# CANBed2040.net
KiCad netlist of a schematic drawn in EAGLE
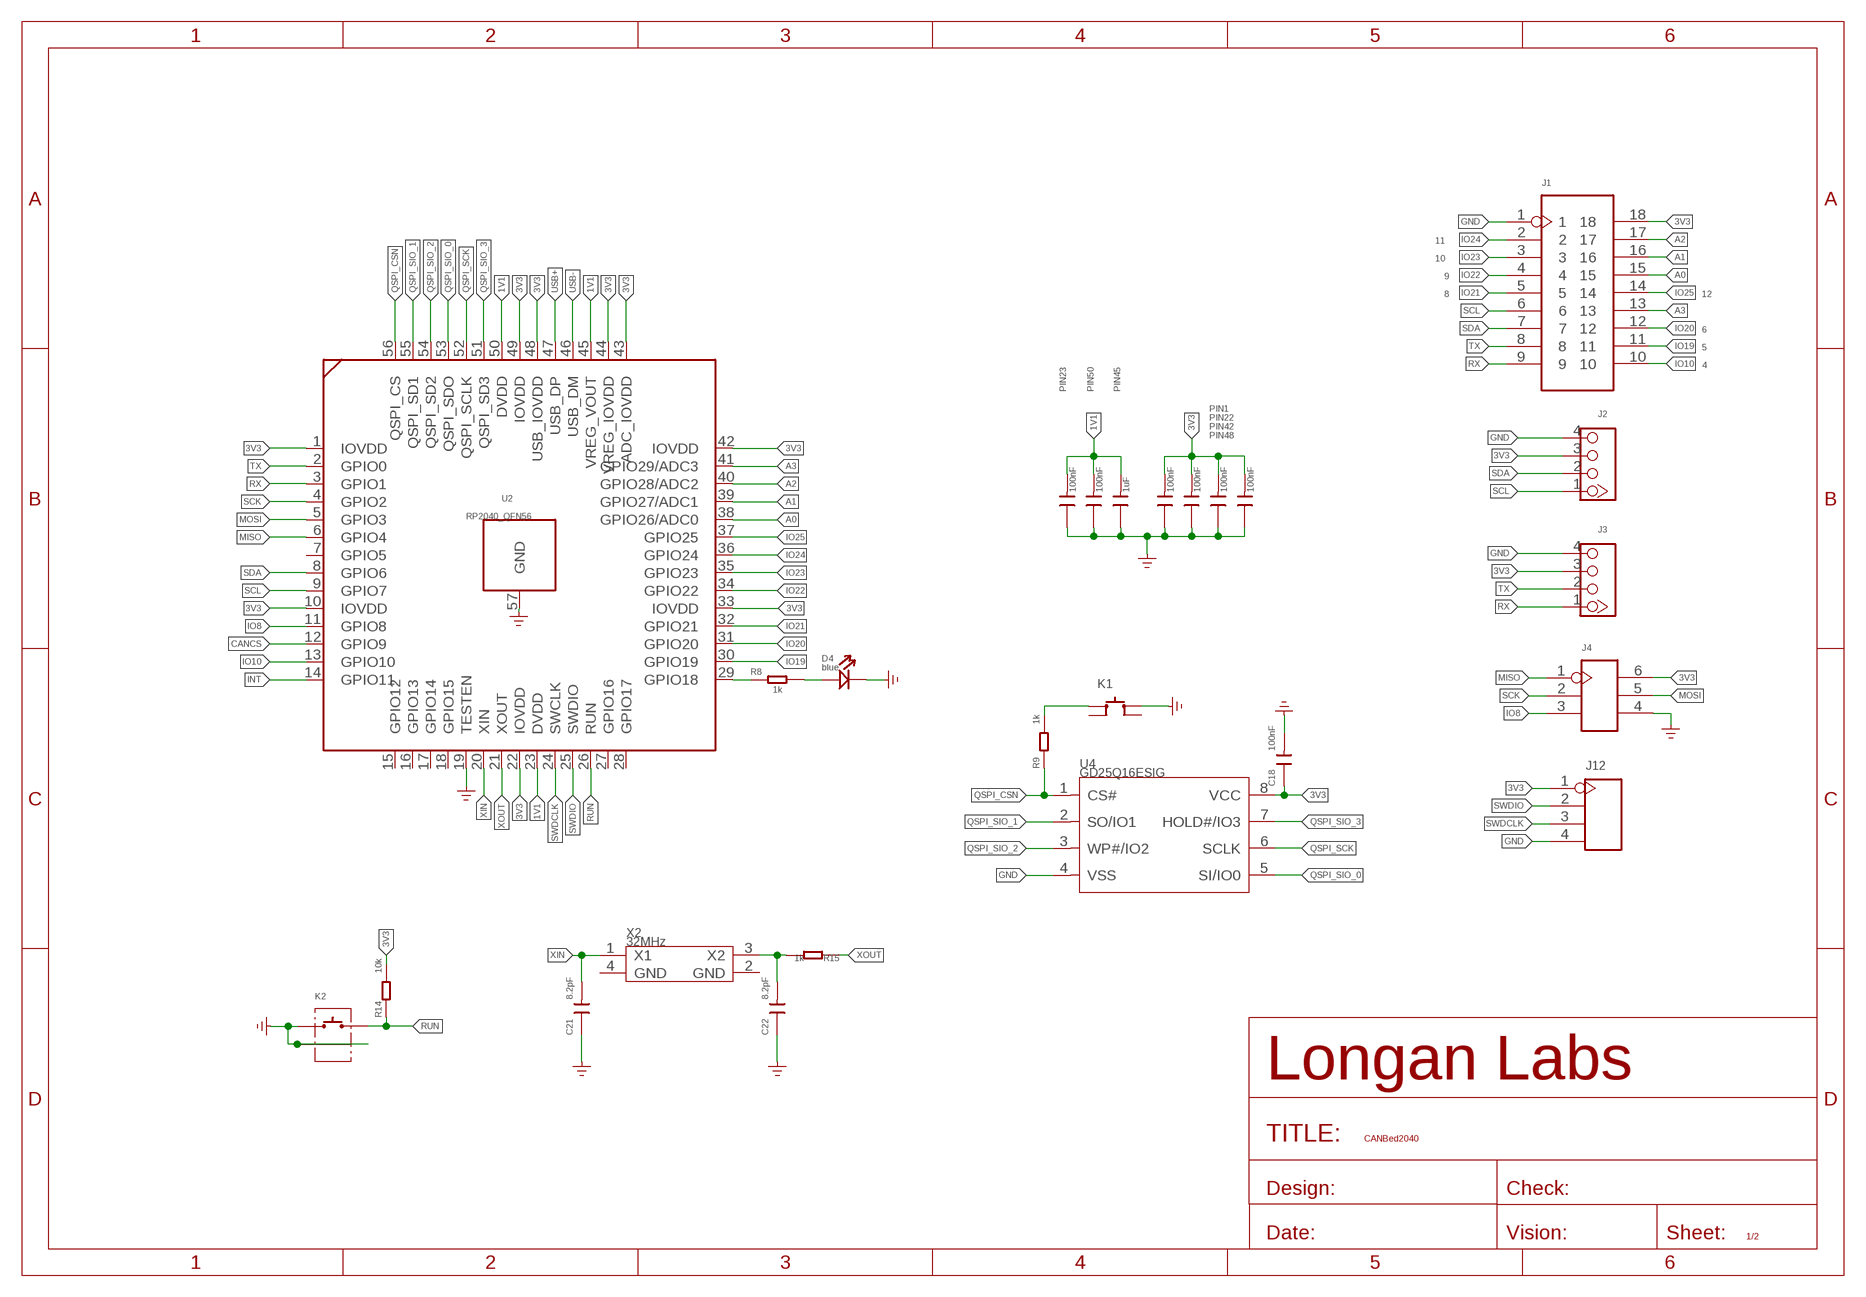
[diagram p0: schematic, sheet 1, part 1 of 2]
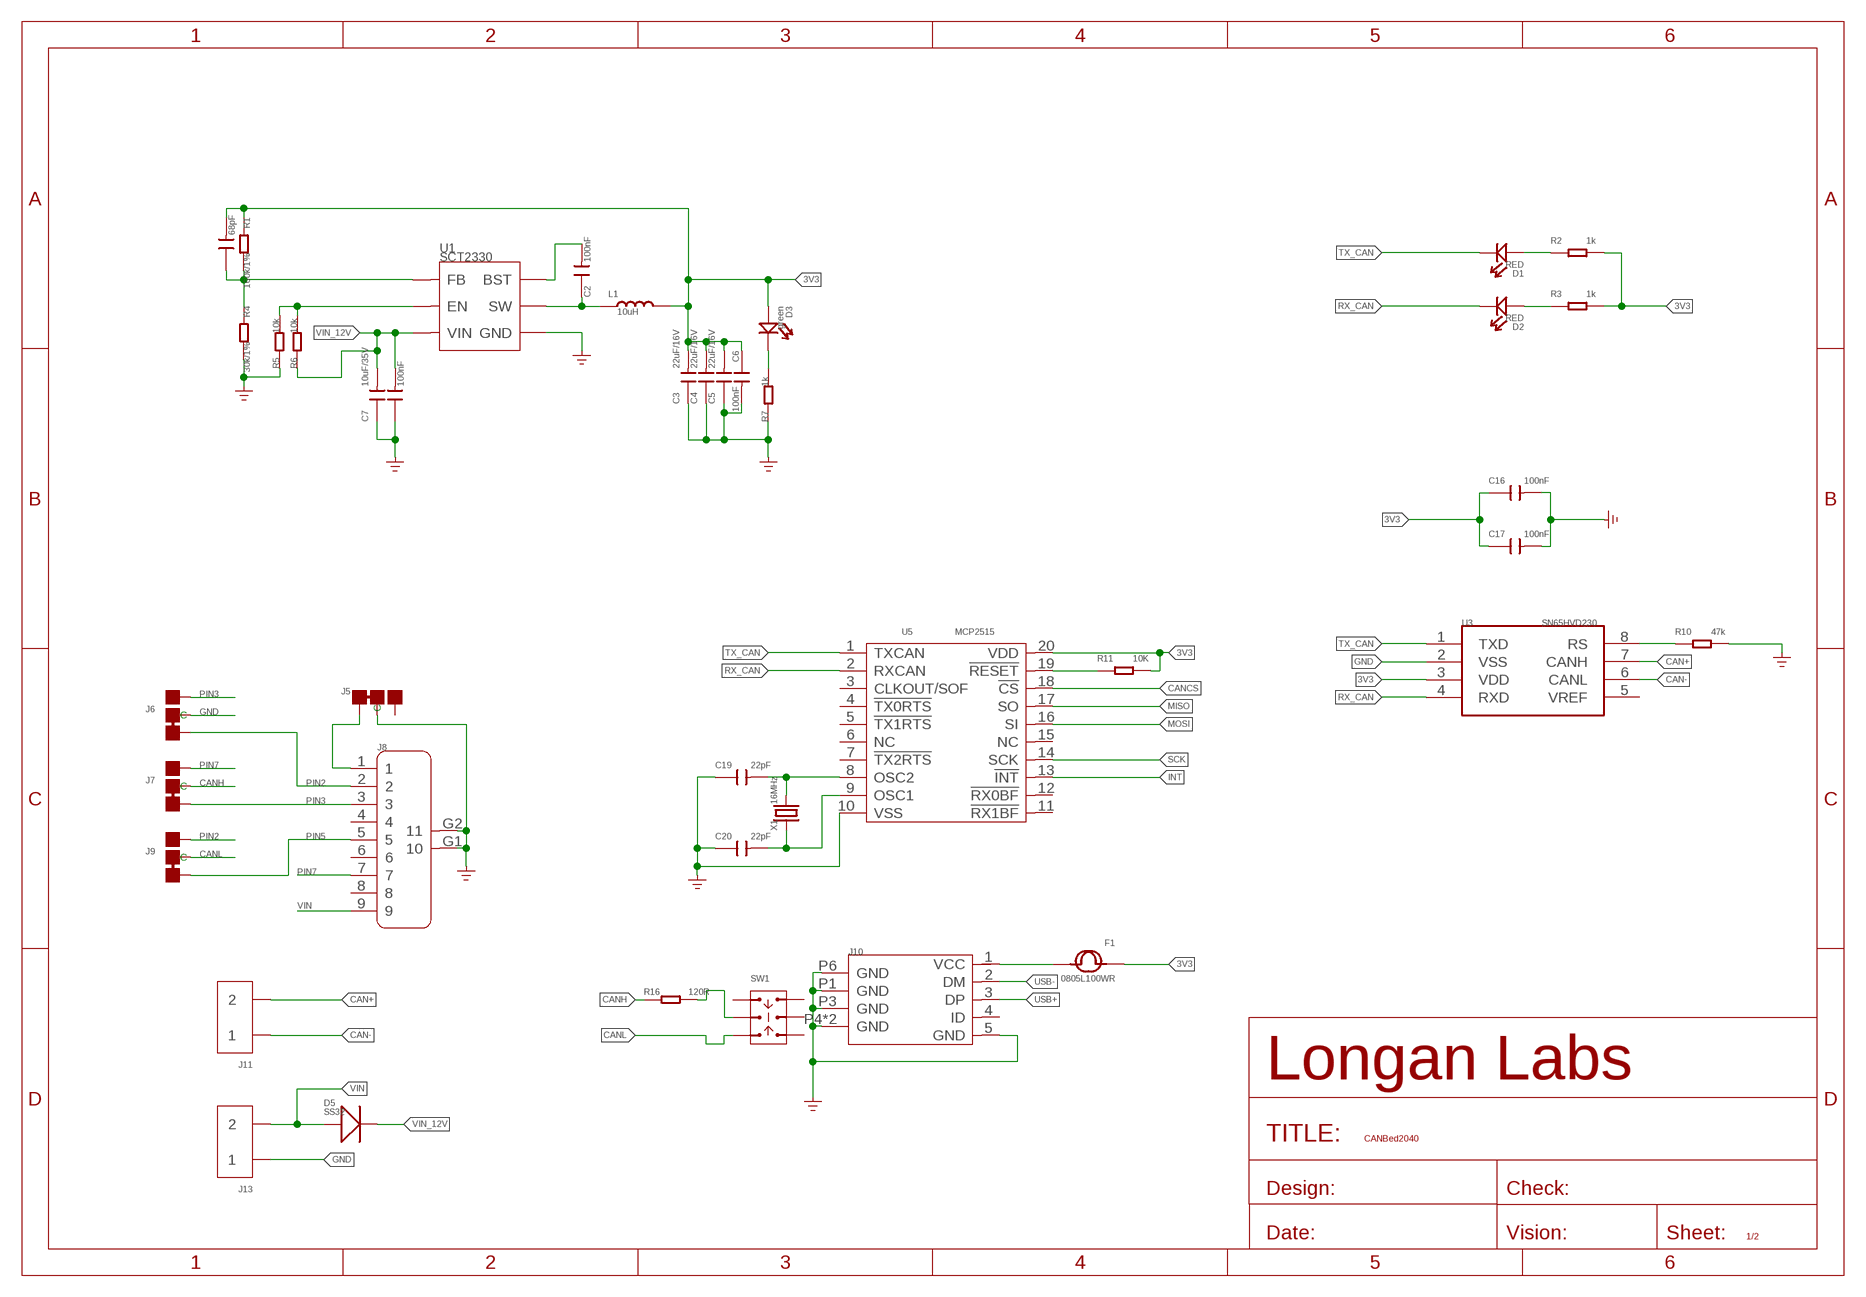
[diagram p1: schematic, sheet 1, part 2 of 2]

(export (version "E")
  (design (tool "Eeschema 10.0.6"))
  (components
    (comp (ref "C1")
      (value "68pF")
      (footprint "eagle-import:C0603")
      (libsource (lib "eagle-import") (part "CAP-0603"))
    )
    (comp (ref "C2")
      (value "100nF")
      (footprint "eagle-import:C0603")
      (libsource (lib "eagle-import") (part "CAP-0603"))
    )
    (comp (ref "C3")
      (value "22uF/16V")
      (footprint "eagle-import:C0805")
      (libsource (lib "eagle-import") (part "CAP-0805"))
    )
    (comp (ref "C4")
      (value "22uF/16V")
      (footprint "eagle-import:C0805")
      (libsource (lib "eagle-import") (part "CAP-0805"))
    )
    (comp (ref "C5")
      (value "22uF/16V")
      (footprint "eagle-import:C0805")
      (libsource (lib "eagle-import") (part "CAP-0805"))
    )
    (comp (ref "C6")
      (value "100nF")
      (footprint "eagle-import:C0603")
      (libsource (lib "eagle-import") (part "CAP-0603"))
    )
    (comp (ref "C7")
      (value "10uF/35V")
      (footprint "eagle-import:C1206")
      (libsource (lib "eagle-import") (part "CAP-1206"))
    )
    (comp (ref "C8")
      (value "100nF")
      (footprint "eagle-import:C0603")
      (libsource (lib "eagle-import") (part "CAP-0603"))
    )
    (comp (ref "C9")
      (value "100nF")
      (footprint "eagle-import:C0603")
      (libsource (lib "eagle-import") (part "CAP-0603"))
    )
    (comp (ref "C10")
      (value "100nF")
      (footprint "eagle-import:C0603")
      (libsource (lib "eagle-import") (part "CAP-0603"))
    )
    (comp (ref "C11")
      (value "1uF")
      (footprint "eagle-import:C0603")
      (libsource (lib "eagle-import") (part "CAP-0603"))
    )
    (comp (ref "C12")
      (value "100nF")
      (footprint "eagle-import:C0603")
      (libsource (lib "eagle-import") (part "CAP-0603"))
    )
    (comp (ref "C13")
      (value "100nF")
      (footprint "eagle-import:C0603")
      (libsource (lib "eagle-import") (part "CAP-0603"))
    )
    (comp (ref "C14")
      (value "100nF")
      (footprint "eagle-import:C0603")
      (libsource (lib "eagle-import") (part "CAP-0603"))
    )
    (comp (ref "C15")
      (value "100nF")
      (footprint "eagle-import:C0603")
      (libsource (lib "eagle-import") (part "CAP-0603"))
    )
    (comp (ref "C16")
      (value "100nF")
      (footprint "eagle-import:C0603")
      (libsource (lib "eagle-import") (part "CAP-0603"))
    )
    (comp (ref "C17")
      (value "100nF")
      (footprint "eagle-import:C0603")
      (libsource (lib "eagle-import") (part "CAP-0603"))
    )
    (comp (ref "C18")
      (value "100nF")
      (footprint "eagle-import:C0603")
      (libsource (lib "eagle-import") (part "CAP-0603"))
    )
    (comp (ref "C19")
      (value "22pF")
      (footprint "eagle-import:C0603")
      (libsource (lib "eagle-import") (part "CAP-0603"))
    )
    (comp (ref "C20")
      (value "22pF")
      (footprint "eagle-import:C0603")
      (libsource (lib "eagle-import") (part "CAP-0603"))
    )
    (comp (ref "C21")
      (value "8.2pF")
      (footprint "eagle-import:C0603")
      (libsource (lib "eagle-import") (part "CAP-0603"))
    )
    (comp (ref "C22")
      (value "8.2pF")
      (footprint "eagle-import:C0603")
      (libsource (lib "eagle-import") (part "CAP-0603"))
    )
    (comp (ref "D1")
      (value "RED")
      (footprint "eagle-import:LED-0603")
      (libsource (lib "eagle-import") (part "LED'0603'"))
    )
    (comp (ref "D2")
      (value "RED")
      (footprint "eagle-import:LED-0603")
      (libsource (lib "eagle-import") (part "LED'0603'"))
    )
    (comp (ref "D3")
      (value "green")
      (footprint "eagle-import:LED-0603")
      (libsource (lib "eagle-import") (part "LED'0603'"))
    )
    (comp (ref "D4")
      (value "blue")
      (footprint "eagle-import:LED-0603")
      (libsource (lib "eagle-import") (part "LED'0603'"))
    )
    (comp (ref "D5")
      (value "SS32")
      (footprint "eagle-import:DO-214AC")
      (libsource (lib "eagle-import") (part "DIODE'SMA'"))
    )
    (comp (ref "F1")
      (value "0805L100WR")
      (footprint "eagle-import:F0805")
      (libsource (lib "eagle-import") (part "FUSE0805"))
    )
    (comp (ref "J1")
      (value "HEADER-2X9P-2.54")
      (footprint "eagle-import:H2X9-2.54")
      (libsource (lib "eagle-import") (part "HEADER-2X9P-2.54"))
    )
    (comp (ref "J2")
      (value "320110033")
      (footprint "eagle-import:HW4-2.0")
      (libsource (lib "eagle-import") (part "GROVE-CONNECTOR-DIP-2.0"))
    )
    (comp (ref "J3")
      (value "320110033")
      (footprint "eagle-import:HW4-2.0")
      (libsource (lib "eagle-import") (part "GROVE-CONNECTOR-DIP-2.0"))
    )
    (comp (ref "J4")
      (value "HEADER-2X3P-2.54")
      (footprint "eagle-import:H2X3-2.54")
      (libsource (lib "eagle-import") (part "HEADER-2X3P-2.54"))
    )
    (comp (ref "J5")
      (value "JUMPER-3P-SHORT")
      (footprint "eagle-import:3P-SMD-SHORT")
      (libsource (lib "eagle-import") (part "JUMPER-3P-SHORT"))
    )
    (comp (ref "J6")
      (value "JUMPER-3P-SHORT")
      (footprint "eagle-import:3P-SMD-SHORT")
      (libsource (lib "eagle-import") (part "JUMPER-3P-SHORT"))
    )
    (comp (ref "J7")
      (value "JUMPER-3P-SHORT")
      (footprint "eagle-import:3P-SMD-SHORT")
      (libsource (lib "eagle-import") (part "JUMPER-3P-SHORT"))
    )
    (comp (ref "J8")
      (value "DB9'MEAL'")
      (footprint "eagle-import:DB9-MEAL")
      (libsource (lib "eagle-import") (part "DB9'MEAL'"))
    )
    (comp (ref "J9")
      (value "JUMPER-3P-SHORT")
      (footprint "eagle-import:3P-SMD-SHORT")
      (libsource (lib "eagle-import") (part "JUMPER-3P-SHORT"))
    )
    (comp (ref "J10")
      (value "MICRO-USB5+4P-320010050")
      (footprint "eagle-import:MICRO-USB5+5P-SMD-0.65-7.2X5.06MM")
      (libsource (lib "eagle-import") (part "MICRO-USB5+4P-320010050"))
    )
    (comp (ref "J11")
      (value "SCREW-TERMINAL-2P'5.08'")
      (footprint "eagle-import:H2-5.0-10.5X8.0MM")
      (libsource (lib "eagle-import") (part "SCREW-TERMINAL-2P'5.08'"))
    )
    (comp (ref "J12")
      (value "HEADER-4P-65/35MIL")
      (footprint "eagle-import:H4-2.54")
      (libsource (lib "eagle-import") (part "HEADER-4P-65/35MIL"))
    )
    (comp (ref "J13")
      (value "SCREW-TERMINAL-2P'5.08'")
      (footprint "eagle-import:H2-5.0-10.5X8.0MM")
      (libsource (lib "eagle-import") (part "SCREW-TERMINAL-2P'5.08'"))
    )
    (comp (ref "K1")
      (value "BUTTON-4P-4.5X4.5")
      (footprint "eagle-import:SW4-4.5X4.5X0.5MM")
      (libsource (lib "eagle-import") (part "BUTTON-4P-4.5X4.5"))
    )
    (comp (ref "K2")
      (value "BUTTON-2+2P")
      (footprint "eagle-import:SW2+2P-7.7X2.75X3.95MM")
      (libsource (lib "eagle-import") (part "BUTTON-2+2P"))
    )
    (comp (ref "L1")
      (value "10uH")
      (footprint "eagle-import:INT2-SMD-6.6X7.1X3MM")
      (libsource (lib "eagle-import") (part "INDUCTOR-6.6X7.1"))
    )
    (comp (ref "R1")
      (value "160k/1%")
      (footprint "eagle-import:R0603")
      (libsource (lib "eagle-import") (part "RES-0603"))
    )
    (comp (ref "R2")
      (value "1k")
      (footprint "eagle-import:R0603")
      (libsource (lib "eagle-import") (part "RES-0603"))
    )
    (comp (ref "R3")
      (value "1k")
      (footprint "eagle-import:R0603")
      (libsource (lib "eagle-import") (part "RES-0603"))
    )
    (comp (ref "R4")
      (value "30k/1%")
      (footprint "eagle-import:R0603")
      (libsource (lib "eagle-import") (part "RES-0603"))
    )
    (comp (ref "R5")
      (value "10k")
      (footprint "eagle-import:R0603")
      (libsource (lib "eagle-import") (part "RES-0603"))
    )
    (comp (ref "R6")
      (value "10k")
      (footprint "eagle-import:R0603")
      (libsource (lib "eagle-import") (part "RES-0603"))
    )
    (comp (ref "R7")
      (value "1k")
      (footprint "eagle-import:R0603")
      (libsource (lib "eagle-import") (part "RES-0603"))
    )
    (comp (ref "R8")
      (value "1k")
      (footprint "eagle-import:R0603")
      (libsource (lib "eagle-import") (part "RES-0603"))
    )
    (comp (ref "R9")
      (value "1k")
      (footprint "eagle-import:R0603")
      (libsource (lib "eagle-import") (part "RES-0603"))
    )
    (comp (ref "R10")
      (value "47k")
      (footprint "eagle-import:R0603")
      (libsource (lib "eagle-import") (part "RES-0603"))
    )
    (comp (ref "R11")
      (value "10K")
      (footprint "eagle-import:R0603")
      (libsource (lib "eagle-import") (part "RES-0603"))
    )
    (comp (ref "R14")
      (value "10k")
      (footprint "eagle-import:R0603")
      (libsource (lib "eagle-import") (part "RES-0603"))
    )
    (comp (ref "R15")
      (value "1k")
      (footprint "eagle-import:R0603")
      (libsource (lib "eagle-import") (part "RES-0603"))
    )
    (comp (ref "R16")
      (value "120R")
      (footprint "eagle-import:R0603")
      (libsource (lib "eagle-import") (part "RES-0603"))
    )
    (comp (ref "SW1")
      (value "SWITCH-2CH-6P-311010004")
      (footprint "eagle-import:SW6-2.54-9.0X3.5X3.2+2.0MM")
      (libsource (lib "eagle-import") (part "SWITCH-2CH-6P-311010004"))
    )
    (comp (ref "U1")
      (value "SCT2330")
      (footprint "eagle-import:SOT-23-6")
      (libsource (lib "eagle-import") (part "PMIC-SCT2330"))
    )
    (comp (ref "U2")
      (value "RP2040_QFN56")
      (footprint "eagle-import:RP2040_QFN56")
      (libsource (lib "eagle-import") (part "RP2040_QFN56"))
    )
    (comp (ref "U3")
      (value "SN65HVD230")
      (footprint "eagle-import:SOIC8-6.0")
      (libsource (lib "eagle-import") (part "MCP2551-SOIC8"))
    )
    (comp (ref "U4")
      (value "GD25Q16ESIG")
      (footprint "eagle-import:SOP8-1.27-5.3X5.25X2MM")
      (libsource (lib "eagle-import") (part "FLASH-GD25Q16E"))
    )
    (comp (ref "U5")
      (value "MCP2515")
      (footprint "eagle-import:TSSOP20-0.65-6.5X4.4MM")
      (libsource (lib "eagle-import") (part "MCP2515'ST'"))
    )
    (comp (ref "X1")
      (value "16MHz")
      (footprint "eagle-import:X4-SMD-3.2X2.5X0.7MM")
      (libsource (lib "eagle-import") (part "CRYSTAL-2P-3225"))
    )
    (comp (ref "X2")
      (value "32MHz")
      (footprint "eagle-import:X4-SMD-3.2X2.5X0.7MM")
      (libsource (lib "eagle-import") (part "CRYSTAL-4P-3225"))
    )
  )
  (nets
    (net (code "1") (name "1V1") (class "Default")
      (node (ref "C10") (pin "2") (pinfunction "2_2") (pintype "passive"))
      (node (ref "C11") (pin "2") (pinfunction "2_2") (pintype "passive"))
      (node (ref "C9") (pin "2") (pinfunction "2_2") (pintype "passive"))
      (node (ref "U2") (pin "23") (pinfunction "DVDD_23") (pintype "bidirectional"))
      (node (ref "U2") (pin "45") (pinfunction "VREG_VOUT_45") (pintype "bidirectional"))
      (node (ref "U2") (pin "50") (pinfunction "DVDD_50") (pintype "bidirectional"))
    )
    (net (code "2") (name "3V3") (class "Default")
      (node (ref "C1") (pin "2") (pinfunction "2_2") (pintype "passive"))
      (node (ref "C12") (pin "2") (pinfunction "2_2") (pintype "passive"))
      (node (ref "C13") (pin "2") (pinfunction "2_2") (pintype "passive"))
      (node (ref "C14") (pin "2") (pinfunction "2_2") (pintype "passive"))
      (node (ref "C15") (pin "2") (pinfunction "2_2") (pintype "passive"))
      (node (ref "C16") (pin "1") (pinfunction "1_1") (pintype "passive"))
      (node (ref "C17") (pin "1") (pinfunction "1_1") (pintype "passive"))
      (node (ref "C18") (pin "1") (pinfunction "1_1") (pintype "passive"))
      (node (ref "C3") (pin "2") (pinfunction "2_2") (pintype "passive"))
      (node (ref "C4") (pin "2") (pinfunction "2_2") (pintype "passive"))
      (node (ref "C5") (pin "2") (pinfunction "2_2") (pintype "passive"))
      (node (ref "C6") (pin "1") (pinfunction "1_1") (pintype "passive"))
      (node (ref "D3") (pin "+") (pinfunction "+_+") (pintype "passive"))
      (node (ref "F1") (pin "1") (pinfunction "1_1") (pintype "bidirectional"))
      (node (ref "J1") (pin "18") (pinfunction "18_18") (pintype "bidirectional"))
      (node (ref "J12") (pin "1") (pinfunction "P$1_1") (pintype "bidirectional"))
      (node (ref "J2") (pin "3") (pinfunction "3_3") (pintype "bidirectional"))
      (node (ref "J3") (pin "3") (pinfunction "3_3") (pintype "bidirectional"))
      (node (ref "J4") (pin "6") (pinfunction "6_6") (pintype "bidirectional"))
      (node (ref "L1") (pin "2") (pinfunction "2_2") (pintype "passive"))
      (node (ref "R1") (pin "1") (pinfunction "1_1") (pintype "passive"))
      (node (ref "R11") (pin "2") (pinfunction "2_2") (pintype "passive"))
      (node (ref "R14") (pin "2") (pinfunction "2_2") (pintype "passive"))
      (node (ref "R2") (pin "2") (pinfunction "2_2") (pintype "passive"))
      (node (ref "R3") (pin "2") (pinfunction "2_2") (pintype "passive"))
      (node (ref "U2") (pin "1") (pinfunction "IOVDD_1") (pintype "bidirectional"))
      (node (ref "U2") (pin "10") (pinfunction "IOVDD_10") (pintype "bidirectional"))
      (node (ref "U2") (pin "22") (pinfunction "IOVDD_22") (pintype "bidirectional"))
      (node (ref "U2") (pin "33") (pinfunction "IOVDD_33") (pintype "bidirectional"))
      (node (ref "U2") (pin "42") (pinfunction "IOVDD_42") (pintype "bidirectional"))
      (node (ref "U2") (pin "43") (pinfunction "ADC_IOVDD_43") (pintype "bidirectional"))
      (node (ref "U2") (pin "44") (pinfunction "VREG_IOVDD_44") (pintype "bidirectional"))
      (node (ref "U2") (pin "48") (pinfunction "USB_IOVDD_48") (pintype "bidirectional"))
      (node (ref "U2") (pin "49") (pinfunction "IOVDD_49") (pintype "bidirectional"))
      (node (ref "U3") (pin "3") (pinfunction "VDD_3") (pintype "bidirectional"))
      (node (ref "U4") (pin "8") (pinfunction "VCC_8") (pintype "bidirectional"))
      (node (ref "U5") (pin "20") (pinfunction "VDD_20") (pintype "bidirectional"))
    )
    (net (code "3") (name "A0") (class "Default")
      (node (ref "J1") (pin "15") (pinfunction "15_15") (pintype "bidirectional"))
      (node (ref "U2") (pin "38") (pinfunction "GPIO26/ADC0_38") (pintype "bidirectional"))
    )
    (net (code "4") (name "A1") (class "Default")
      (node (ref "J1") (pin "16") (pinfunction "16_16") (pintype "bidirectional"))
      (node (ref "U2") (pin "39") (pinfunction "GPIO27/ADC1_39") (pintype "bidirectional"))
    )
    (net (code "5") (name "A2") (class "Default")
      (node (ref "J1") (pin "17") (pinfunction "17_17") (pintype "bidirectional"))
      (node (ref "U2") (pin "40") (pinfunction "GPIO28/ADC2_40") (pintype "bidirectional"))
    )
    (net (code "6") (name "A3") (class "Default")
      (node (ref "J1") (pin "13") (pinfunction "13_13") (pintype "bidirectional"))
      (node (ref "U2") (pin "41") (pinfunction "GPIO29/ADC3_41") (pintype "bidirectional"))
    )
    (net (code "7") (name "CAN+") (class "Default")
      (node (ref "J11") (pin "2") (pinfunction "2_2") (pintype "bidirectional"))
      (node (ref "U3") (pin "7") (pinfunction "CANH_7") (pintype "bidirectional"))
    )
    (net (code "8") (name "CAN-") (class "Default")
      (node (ref "J11") (pin "1") (pinfunction "1_1") (pintype "bidirectional"))
      (node (ref "U3") (pin "6") (pinfunction "CANL_6") (pintype "bidirectional"))
    )
    (net (code "9") (name "CANCS") (class "Default")
      (node (ref "U2") (pin "12") (pinfunction "GPIO9_12") (pintype "bidirectional"))
      (node (ref "U5") (pin "18") (pinfunction "~{CS}_18") (pintype "bidirectional"))
    )
    (net (code "10") (name "CANH") (class "Default")
      (node (ref "J7") (pin "MM") (pinfunction "C_MM") (pintype "bidirectional"))
      (node (ref "R16") (pin "1") (pinfunction "1_1") (pintype "passive"))
    )
    (net (code "11") (name "CANL") (class "Default")
      (node (ref "J9") (pin "MM") (pinfunction "C_MM") (pintype "bidirectional"))
      (node (ref "SW1") (pin "CH1B") (pinfunction "CH1B_CH1B") (pintype "bidirectional"))
    )
    (net (code "12") (name "GND") (class "Default")
      (node (ref "C10") (pin "1") (pinfunction "1_1") (pintype "passive"))
      (node (ref "C11") (pin "1") (pinfunction "1_1") (pintype "passive"))
      (node (ref "C12") (pin "1") (pinfunction "1_1") (pintype "passive"))
      (node (ref "C13") (pin "1") (pinfunction "1_1") (pintype "passive"))
      (node (ref "C14") (pin "1") (pinfunction "1_1") (pintype "passive"))
      (node (ref "C15") (pin "1") (pinfunction "1_1") (pintype "passive"))
      (node (ref "C16") (pin "2") (pinfunction "2_2") (pintype "passive"))
      (node (ref "C17") (pin "2") (pinfunction "2_2") (pintype "passive"))
      (node (ref "C18") (pin "2") (pinfunction "2_2") (pintype "passive"))
      (node (ref "C19") (pin "1") (pinfunction "1_1") (pintype "passive"))
      (node (ref "C20") (pin "1") (pinfunction "1_1") (pintype "passive"))
      (node (ref "C21") (pin "1") (pinfunction "1_1") (pintype "passive"))
      (node (ref "C22") (pin "1") (pinfunction "1_1") (pintype "passive"))
      (node (ref "C3") (pin "1") (pinfunction "1_1") (pintype "passive"))
      (node (ref "C4") (pin "1") (pinfunction "1_1") (pintype "passive"))
      (node (ref "C5") (pin "1") (pinfunction "1_1") (pintype "passive"))
      (node (ref "C6") (pin "2") (pinfunction "2_2") (pintype "passive"))
      (node (ref "C7") (pin "1") (pinfunction "1_1") (pintype "passive"))
      (node (ref "C8") (pin "1") (pinfunction "1_1") (pintype "passive"))
      (node (ref "C9") (pin "1") (pinfunction "1_1") (pintype "passive"))
      (node (ref "D4") (pin "-") (pinfunction "-_-") (pintype "passive"))
      (node (ref "J1") (pin "1") (pinfunction "1_1") (pintype "bidirectional"))
      (node (ref "J10") (pin "5") (pinfunction "GND_5") (pintype "bidirectional"))
      (node (ref "J10") (pin "P1") (pinfunction "GND_P1") (pintype "bidirectional"))
      (node (ref "J10") (pin "P3") (pinfunction "GND_P3") (pintype "bidirectional"))
      (node (ref "J10") (pin "P4") (pinfunction "GND_P4") (pintype "bidirectional"))
      (node (ref "J10") (pin "P5") (pinfunction "GND_P5") (pintype "bidirectional"))
      (node (ref "J10") (pin "P6") (pinfunction "GND_P6") (pintype "bidirectional"))
      (node (ref "J12") (pin "4") (pinfunction "P$4_4") (pintype "bidirectional"))
      (node (ref "J13") (pin "1") (pinfunction "1_1") (pintype "bidirectional"))
      (node (ref "J2") (pin "4") (pinfunction "4_4") (pintype "bidirectional"))
      (node (ref "J3") (pin "4") (pinfunction "4_4") (pintype "bidirectional"))
      (node (ref "J4") (pin "4") (pinfunction "4_4") (pintype "bidirectional"))
      (node (ref "J5") (pin "MM") (pinfunction "C_MM") (pintype "bidirectional"))
      (node (ref "J6") (pin "MM") (pinfunction "C_MM") (pintype "bidirectional"))
      (node (ref "J8") (pin "G1") (pinfunction "10_G1") (pintype "bidirectional"))
      (node (ref "J8") (pin "G2") (pinfunction "11_G2") (pintype "bidirectional"))
      (node (ref "K1") (pin "3") (pinfunction "B0_3") (pintype "bidirectional"))
      (node (ref "K2") (pin "1") (pinfunction "1_1") (pintype "bidirectional"))
      (node (ref "K2") (pin "S1") (pinfunction "S1_S1") (pintype "bidirectional"))
      (node (ref "K2") (pin "S2") (pinfunction "S2_S2") (pintype "bidirectional"))
      (node (ref "R10") (pin "2") (pinfunction "2_2") (pintype "passive"))
      (node (ref "R4") (pin "2") (pinfunction "2_2") (pintype "passive"))
      (node (ref "R5") (pin "1") (pinfunction "1_1") (pintype "passive"))
      (node (ref "R7") (pin "1") (pinfunction "1_1") (pintype "passive"))
      (node (ref "U1") (pin "4") (pinfunction "GND_4") (pintype "bidirectional"))
      (node (ref "U2") (pin "19") (pinfunction "TESTEN_19") (pintype "bidirectional"))
      (node (ref "U2") (pin "57") (pinfunction "GND_57") (pintype "bidirectional"))
      (node (ref "U3") (pin "2") (pinfunction "VSS_2") (pintype "bidirectional"))
      (node (ref "U4") (pin "4") (pinfunction "VSS_4") (pintype "bidirectional"))
      (node (ref "U5") (pin "10") (pinfunction "VSS_10") (pintype "bidirectional"))
    )
    (net (code "13") (name "INT") (class "Default")
      (node (ref "U2") (pin "14") (pinfunction "GPIO11_14") (pintype "bidirectional"))
      (node (ref "U5") (pin "13") (pinfunction "~{INT}_13") (pintype "bidirectional"))
    )
    (net (code "14") (name "IO8") (class "Default")
      (node (ref "J4") (pin "3") (pinfunction "3_3") (pintype "bidirectional"))
      (node (ref "U2") (pin "11") (pinfunction "GPIO8_11") (pintype "bidirectional"))
    )
    (net (code "15") (name "IO10") (class "Default")
      (node (ref "J1") (pin "10") (pinfunction "10_10") (pintype "bidirectional"))
      (node (ref "U2") (pin "13") (pinfunction "GPIO10_13") (pintype "bidirectional"))
    )
    (net (code "16") (name "IO19") (class "Default")
      (node (ref "J1") (pin "11") (pinfunction "11_11") (pintype "bidirectional"))
      (node (ref "U2") (pin "30") (pinfunction "GPIO19_30") (pintype "bidirectional"))
    )
    (net (code "17") (name "IO20") (class "Default")
      (node (ref "J1") (pin "12") (pinfunction "12_12") (pintype "bidirectional"))
      (node (ref "U2") (pin "31") (pinfunction "GPIO20_31") (pintype "bidirectional"))
    )
    (net (code "18") (name "IO21") (class "Default")
      (node (ref "J1") (pin "5") (pinfunction "5_5") (pintype "bidirectional"))
      (node (ref "U2") (pin "32") (pinfunction "GPIO21_32") (pintype "bidirectional"))
    )
    (net (code "19") (name "IO22") (class "Default")
      (node (ref "J1") (pin "4") (pinfunction "4_4") (pintype "bidirectional"))
      (node (ref "U2") (pin "34") (pinfunction "GPIO22_34") (pintype "bidirectional"))
    )
    (net (code "20") (name "IO23") (class "Default")
      (node (ref "J1") (pin "3") (pinfunction "3_3") (pintype "bidirectional"))
      (node (ref "U2") (pin "35") (pinfunction "GPIO23_35") (pintype "bidirectional"))
    )
    (net (code "21") (name "IO24") (class "Default")
      (node (ref "J1") (pin "2") (pinfunction "2_2") (pintype "bidirectional"))
      (node (ref "U2") (pin "36") (pinfunction "GPIO24_36") (pintype "bidirectional"))
    )
    (net (code "22") (name "IO25") (class "Default")
      (node (ref "J1") (pin "14") (pinfunction "14_14") (pintype "bidirectional"))
      (node (ref "U2") (pin "37") (pinfunction "GPIO25_37") (pintype "bidirectional"))
    )
    (net (code "23") (name "MISO") (class "Default")
      (node (ref "J4") (pin "1") (pinfunction "1_1") (pintype "bidirectional"))
      (node (ref "U2") (pin "6") (pinfunction "GPIO4_6") (pintype "bidirectional"))
      (node (ref "U5") (pin "17") (pinfunction "SO_17") (pintype "bidirectional"))
    )
    (net (code "24") (name "MOSI") (class "Default")
      (node (ref "J4") (pin "5") (pinfunction "5_5") (pintype "bidirectional"))
      (node (ref "U2") (pin "5") (pinfunction "GPIO3_5") (pintype "bidirectional"))
      (node (ref "U5") (pin "16") (pinfunction "SI_16") (pintype "bidirectional"))
    )
    (net (code "25") (name "Net-(D1-Pad+)") (class "Default")
      (node (ref "D1") (pin "+") (pinfunction "+_+") (pintype "passive"))
      (node (ref "R2") (pin "1") (pinfunction "1_1") (pintype "passive"))
    )
    (net (code "26") (name "Net-(D2-Pad+)") (class "Default")
      (node (ref "D2") (pin "+") (pinfunction "+_+") (pintype "passive"))
      (node (ref "R3") (pin "1") (pinfunction "1_1") (pintype "passive"))
    )
    (net (code "27") (name "Net-(D3-Pad-)") (class "Default")
      (node (ref "D3") (pin "-") (pinfunction "-_-") (pintype "passive"))
      (node (ref "R7") (pin "2") (pinfunction "2_2") (pintype "passive"))
    )
    (net (code "28") (name "Net-(D4-Pad+)") (class "Default")
      (node (ref "D4") (pin "+") (pinfunction "+_+") (pintype "passive"))
      (node (ref "R8") (pin "2") (pinfunction "2_2") (pintype "passive"))
    )
    (net (code "29") (name "Net-(J5-L)") (class "Default")
      (node (ref "J5") (pin "11") (pinfunction "L_11") (pintype "bidirectional"))
      (node (ref "J8") (pin "1") (pinfunction "1_1") (pintype "bidirectional"))
    )
    (net (code "30") (name "Net-(J10-VCC)") (class "Default")
      (node (ref "F1") (pin "2") (pinfunction "2_2") (pintype "bidirectional"))
      (node (ref "J10") (pin "1") (pinfunction "VCC_1") (pintype "bidirectional"))
    )
    (net (code "31") (name "Net-(K1-A0)") (class "Default")
      (node (ref "K1") (pin "1") (pinfunction "A0_1") (pintype "bidirectional"))
      (node (ref "R9") (pin "2") (pinfunction "2_2") (pintype "passive"))
    )
    (net (code "32") (name "Net-(R16-Pad2)") (class "Default")
      (node (ref "R16") (pin "2") (pinfunction "2_2") (pintype "passive"))
      (node (ref "SW1") (pin "COM1") (pinfunction "COM1_COM1") (pintype "bidirectional"))
    )
    (net (code "33") (name "Net-(U1-BST)") (class "Default")
      (node (ref "C2") (pin "2") (pinfunction "2_2") (pintype "passive"))
      (node (ref "U1") (pin "6") (pinfunction "BST_6") (pintype "bidirectional"))
    )
    (net (code "34") (name "Net-(U1-EN)") (class "Default")
      (node (ref "R5") (pin "2") (pinfunction "2_2") (pintype "passive"))
      (node (ref "R6") (pin "2") (pinfunction "2_2") (pintype "passive"))
      (node (ref "U1") (pin "2") (pinfunction "EN_2") (pintype "bidirectional"))
    )
    (net (code "35") (name "Net-(U1-FB)") (class "Default")
      (node (ref "C1") (pin "1") (pinfunction "1_1") (pintype "passive"))
      (node (ref "R1") (pin "2") (pinfunction "2_2") (pintype "passive"))
      (node (ref "R4") (pin "1") (pinfunction "1_1") (pintype "passive"))
      (node (ref "U1") (pin "1") (pinfunction "FB_1") (pintype "bidirectional"))
    )
    (net (code "36") (name "Net-(U1-SW)") (class "Default")
      (node (ref "C2") (pin "1") (pinfunction "1_1") (pintype "passive"))
      (node (ref "L1") (pin "1") (pinfunction "1_1") (pintype "passive"))
      (node (ref "U1") (pin "5") (pinfunction "SW_5") (pintype "bidirectional"))
    )
    (net (code "37") (name "Net-(U2-GPIO18)") (class "Default")
      (node (ref "R8") (pin "1") (pinfunction "1_1") (pintype "passive"))
      (node (ref "U2") (pin "29") (pinfunction "GPIO18_29") (pintype "bidirectional"))
    )
    (net (code "38") (name "Net-(U3-RS)") (class "Default")
      (node (ref "R10") (pin "1") (pinfunction "1_1") (pintype "passive"))
      (node (ref "U3") (pin "8") (pinfunction "RS_8") (pintype "bidirectional"))
    )
    (net (code "39") (name "Net-(U5-OSC1)") (class "Default")
      (node (ref "C20") (pin "2") (pinfunction "2_2") (pintype "passive"))
      (node (ref "U5") (pin "9") (pinfunction "OSC1_9") (pintype "bidirectional"))
      (node (ref "X1") (pin "1") (pinfunction "1_1") (pintype "passive"))
    )
    (net (code "40") (name "Net-(U5-OSC2)") (class "Default")
      (node (ref "C19") (pin "2") (pinfunction "2_2") (pintype "passive"))
      (node (ref "U5") (pin "8") (pinfunction "OSC2_8") (pintype "bidirectional"))
      (node (ref "X1") (pin "3") (pinfunction "2_3") (pintype "passive"))
    )
    (net (code "41") (name "Net-(U5-~{RESET})") (class "Default")
      (node (ref "R11") (pin "1") (pinfunction "1_1") (pintype "passive"))
      (node (ref "U5") (pin "19") (pinfunction "~{RESET}_19") (pintype "bidirectional"))
    )
    (net (code "42") (name "Net-(X2-X2)") (class "Default")
      (node (ref "C22") (pin "2") (pinfunction "2_2") (pintype "passive"))
      (node (ref "R15") (pin "2") (pinfunction "2_2") (pintype "passive"))
      (node (ref "X2") (pin "3") (pinfunction "X2_3") (pintype "bidirectional"))
    )
    (net (code "43") (name "PIN2") (class "Default")
      (node (ref "J6") (pin "11") (pinfunction "L_11") (pintype "bidirectional"))
      (node (ref "J8") (pin "2") (pinfunction "2_2") (pintype "bidirectional"))
      (node (ref "J9") (pin "00") (pinfunction "R_00") (pintype "bidirectional"))
    )
    (net (code "44") (name "PIN3") (class "Default")
      (node (ref "J6") (pin "00") (pinfunction "R_00") (pintype "bidirectional"))
      (node (ref "J7") (pin "11") (pinfunction "L_11") (pintype "bidirectional"))
      (node (ref "J8") (pin "3") (pinfunction "3_3") (pintype "bidirectional"))
    )
    (net (code "45") (name "PIN5") (class "Default")
      (node (ref "J8") (pin "5") (pinfunction "5_5") (pintype "bidirectional"))
      (node (ref "J9") (pin "11") (pinfunction "L_11") (pintype "bidirectional"))
    )
    (net (code "46") (name "PIN7") (class "Default")
      (node (ref "J7") (pin "00") (pinfunction "R_00") (pintype "bidirectional"))
      (node (ref "J8") (pin "7") (pinfunction "7_7") (pintype "bidirectional"))
    )
    (net (code "47") (name "QSPI_CSN") (class "Default")
      (node (ref "R9") (pin "1") (pinfunction "1_1") (pintype "passive"))
      (node (ref "U2") (pin "56") (pinfunction "QSPI_CS_56") (pintype "bidirectional"))
      (node (ref "U4") (pin "1") (pinfunction "CS#_1") (pintype "bidirectional"))
    )
    (net (code "48") (name "QSPI_SCK") (class "Default")
      (node (ref "U2") (pin "52") (pinfunction "QSPI_SCLK_52") (pintype "bidirectional"))
      (node (ref "U4") (pin "6") (pinfunction "SCLK_6") (pintype "bidirectional"))
    )
    (net (code "49") (name "QSPI_SIO_0") (class "Default")
      (node (ref "U2") (pin "53") (pinfunction "QSPI_SDO_53") (pintype "bidirectional"))
      (node (ref "U4") (pin "5") (pinfunction "SI/IO0_5") (pintype "bidirectional"))
    )
    (net (code "50") (name "QSPI_SIO_1") (class "Default")
      (node (ref "U2") (pin "55") (pinfunction "QSPI_SD1_55") (pintype "bidirectional"))
      (node (ref "U4") (pin "2") (pinfunction "SO/IO1_2") (pintype "bidirectional"))
    )
    (net (code "51") (name "QSPI_SIO_2") (class "Default")
      (node (ref "U2") (pin "54") (pinfunction "QSPI_SD2_54") (pintype "bidirectional"))
      (node (ref "U4") (pin "3") (pinfunction "WP#/IO2_3") (pintype "bidirectional"))
    )
    (net (code "52") (name "QSPI_SIO_3") (class "Default")
      (node (ref "U2") (pin "51") (pinfunction "QSPI_SD3_51") (pintype "bidirectional"))
      (node (ref "U4") (pin "7") (pinfunction "HOLD#/IO3_7") (pintype "bidirectional"))
    )
    (net (code "53") (name "RUN") (class "Default")
      (node (ref "K2") (pin "2") (pinfunction "2_2") (pintype "bidirectional"))
      (node (ref "R14") (pin "1") (pinfunction "1_1") (pintype "passive"))
      (node (ref "U2") (pin "26") (pinfunction "RUN_26") (pintype "bidirectional"))
    )
    (net (code "54") (name "RX") (class "Default")
      (node (ref "J1") (pin "9") (pinfunction "9_9") (pintype "bidirectional"))
      (node (ref "J3") (pin "1") (pinfunction "1_1") (pintype "bidirectional"))
      (node (ref "U2") (pin "3") (pinfunction "GPIO1_3") (pintype "bidirectional"))
    )
    (net (code "55") (name "RX_CAN") (class "Default")
      (node (ref "D2") (pin "-") (pinfunction "-_-") (pintype "passive"))
      (node (ref "U3") (pin "4") (pinfunction "RXD_4") (pintype "bidirectional"))
      (node (ref "U5") (pin "2") (pinfunction "RXCAN_2") (pintype "bidirectional"))
    )
    (net (code "56") (name "SCK") (class "Default")
      (node (ref "J4") (pin "2") (pinfunction "2_2") (pintype "bidirectional"))
      (node (ref "U2") (pin "4") (pinfunction "GPIO2_4") (pintype "bidirectional"))
      (node (ref "U5") (pin "14") (pinfunction "SCK_14") (pintype "bidirectional"))
    )
    (net (code "57") (name "SCL") (class "Default")
      (node (ref "J1") (pin "6") (pinfunction "6_6") (pintype "bidirectional"))
      (node (ref "J2") (pin "1") (pinfunction "1_1") (pintype "bidirectional"))
      (node (ref "U2") (pin "9") (pinfunction "GPIO7_9") (pintype "bidirectional"))
    )
    (net (code "58") (name "SDA") (class "Default")
      (node (ref "J1") (pin "7") (pinfunction "7_7") (pintype "bidirectional"))
      (node (ref "J2") (pin "2") (pinfunction "2_2") (pintype "bidirectional"))
      (node (ref "U2") (pin "8") (pinfunction "GPIO6_8") (pintype "bidirectional"))
    )
    (net (code "59") (name "SWDCLK") (class "Default")
      (node (ref "J12") (pin "3") (pinfunction "P$3_3") (pintype "bidirectional"))
      (node (ref "U2") (pin "24") (pinfunction "SWCLK_24") (pintype "bidirectional"))
    )
    (net (code "60") (name "SWDIO") (class "Default")
      (node (ref "J12") (pin "2") (pinfunction "P$2_2") (pintype "bidirectional"))
      (node (ref "U2") (pin "25") (pinfunction "SWDIO_25") (pintype "bidirectional"))
    )
    (net (code "61") (name "TX") (class "Default")
      (node (ref "J1") (pin "8") (pinfunction "8_8") (pintype "bidirectional"))
      (node (ref "J3") (pin "2") (pinfunction "2_2") (pintype "bidirectional"))
      (node (ref "U2") (pin "2") (pinfunction "GPIO0_2") (pintype "bidirectional"))
    )
    (net (code "62") (name "TX_CAN") (class "Default")
      (node (ref "D1") (pin "-") (pinfunction "-_-") (pintype "passive"))
      (node (ref "U3") (pin "1") (pinfunction "TXD_1") (pintype "bidirectional"))
      (node (ref "U5") (pin "1") (pinfunction "TXCAN_1") (pintype "bidirectional"))
    )
    (net (code "63") (name "USB+") (class "Default")
      (node (ref "J10") (pin "3") (pinfunction "DP_3") (pintype "bidirectional"))
      (node (ref "U2") (pin "47") (pinfunction "USB_DP_47") (pintype "bidirectional"))
    )
    (net (code "64") (name "USB-") (class "Default")
      (node (ref "J10") (pin "2") (pinfunction "DM_2") (pintype "bidirectional"))
      (node (ref "U2") (pin "46") (pinfunction "USB_DM_46") (pintype "bidirectional"))
    )
    (net (code "65") (name "VIN") (class "Default")
      (node (ref "D5") (pin "1") (pinfunction "+_1") (pintype "passive"))
      (node (ref "J13") (pin "2") (pinfunction "2_2") (pintype "bidirectional"))
      (node (ref "J8") (pin "9") (pinfunction "9_9") (pintype "bidirectional"))
    )
    (net (code "66") (name "VIN_12V") (class "Default")
      (node (ref "C7") (pin "2") (pinfunction "2_2") (pintype "passive"))
      (node (ref "C8") (pin "2") (pinfunction "2_2") (pintype "passive"))
      (node (ref "D5") (pin "2") (pinfunction "-_2") (pintype "passive"))
      (node (ref "R6") (pin "1") (pinfunction "1_1") (pintype "passive"))
      (node (ref "U1") (pin "3") (pinfunction "VIN_3") (pintype "bidirectional"))
    )
    (net (code "67") (name "XIN") (class "Default")
      (node (ref "C21") (pin "2") (pinfunction "2_2") (pintype "passive"))
      (node (ref "U2") (pin "20") (pinfunction "XIN_20") (pintype "bidirectional"))
      (node (ref "X2") (pin "1") (pinfunction "X1_1") (pintype "bidirectional"))
    )
    (net (code "68") (name "XOUT") (class "Default")
      (node (ref "R15") (pin "1") (pinfunction "1_1") (pintype "passive"))
      (node (ref "U2") (pin "21") (pinfunction "XOUT_21") (pintype "bidirectional"))
    )
    (net (code "69") (name "unconnected-(J5-R-Pad00)") (class "Default")
      (node (ref "J5") (pin "00") (pinfunction "R_00") (pintype "bidirectional"))
    )
    (net (code "70") (name "unconnected-(J8-Pad4)") (class "Default")
      (node (ref "J8") (pin "4") (pinfunction "4_4") (pintype "bidirectional"))
    )
    (net (code "71") (name "unconnected-(J8-Pad6)") (class "Default")
      (node (ref "J8") (pin "6") (pinfunction "6_6") (pintype "bidirectional"))
    )
    (net (code "72") (name "unconnected-(J8-Pad8)") (class "Default")
      (node (ref "J8") (pin "8") (pinfunction "8_8") (pintype "bidirectional"))
    )
    (net (code "73") (name "unconnected-(J10-ID-Pad4)") (class "Default")
      (node (ref "J10") (pin "4") (pinfunction "ID_4") (pintype "bidirectional"))
    )
    (net (code "74") (name "unconnected-(K1-A1-Pad2)") (class "Default")
      (node (ref "K1") (pin "2") (pinfunction "A1_2") (pintype "bidirectional"))
    )
    (net (code "75") (name "unconnected-(K1-B1-Pad4)") (class "Default")
      (node (ref "K1") (pin "4") (pinfunction "B1_4") (pintype "bidirectional"))
    )
    (net (code "76") (name "unconnected-(SW1-PadCH1A)") (class "Default")
      (node (ref "SW1") (pin "CH1A") (pinfunction "CH1A_CH1A") (pintype "bidirectional"))
    )
    (net (code "77") (name "unconnected-(SW1-PadCH2A)") (class "Default")
      (node (ref "SW1") (pin "CH2A") (pinfunction "CH2A_CH2A") (pintype "bidirectional"))
    )
    (net (code "78") (name "unconnected-(SW1-PadCH2B)") (class "Default")
      (node (ref "SW1") (pin "CH2B") (pinfunction "CH2B_CH2B") (pintype "bidirectional"))
    )
    (net (code "79") (name "unconnected-(SW1-PadCOM2)") (class "Default")
      (node (ref "SW1") (pin "COM2") (pinfunction "COM2_COM2") (pintype "bidirectional"))
    )
    (net (code "80") (name "unconnected-(U2-GPIO5-Pad7)") (class "Default")
      (node (ref "U2") (pin "7") (pinfunction "GPIO5_7") (pintype "bidirectional"))
    )
    (net (code "81") (name "unconnected-(U2-GPIO12-Pad15)") (class "Default")
      (node (ref "U2") (pin "15") (pinfunction "GPIO12_15") (pintype "bidirectional"))
    )
    (net (code "82") (name "unconnected-(U2-GPIO13-Pad16)") (class "Default")
      (node (ref "U2") (pin "16") (pinfunction "GPIO13_16") (pintype "bidirectional"))
    )
    (net (code "83") (name "unconnected-(U2-GPIO14-Pad17)") (class "Default")
      (node (ref "U2") (pin "17") (pinfunction "GPIO14_17") (pintype "bidirectional"))
    )
    (net (code "84") (name "unconnected-(U2-GPIO15-Pad18)") (class "Default")
      (node (ref "U2") (pin "18") (pinfunction "GPIO15_18") (pintype "bidirectional"))
    )
    (net (code "85") (name "unconnected-(U2-GPIO16-Pad27)") (class "Default")
      (node (ref "U2") (pin "27") (pinfunction "GPIO16_27") (pintype "bidirectional"))
    )
    (net (code "86") (name "unconnected-(U2-GPIO17-Pad28)") (class "Default")
      (node (ref "U2") (pin "28") (pinfunction "GPIO17_28") (pintype "bidirectional"))
    )
    (net (code "87") (name "unconnected-(U3-VREF-Pad5)") (class "Default")
      (node (ref "U3") (pin "5") (pinfunction "VREF_5") (pintype "bidirectional"))
    )
    (net (code "88") (name "unconnected-(U5-CLKOUT{slash}SOF-Pad3)") (class "Default")
      (node (ref "U5") (pin "3") (pinfunction "CLKOUT/SOF_3") (pintype "bidirectional"))
    )
    (net (code "89") (name "unconnected-(U5-NC-Pad6)") (class "Default")
      (node (ref "U5") (pin "6") (pinfunction "NC_6") (pintype "bidirectional"))
    )
    (net (code "90") (name "unconnected-(U5-NC-Pad15)") (class "Default")
      (node (ref "U5") (pin "15") (pinfunction "NC_15") (pintype "bidirectional"))
    )
    (net (code "91") (name "unconnected-(U5-~{RX0BF}-Pad12)") (class "Default")
      (node (ref "U5") (pin "12") (pinfunction "~{RX0BF}_12") (pintype "bidirectional"))
    )
    (net (code "92") (name "unconnected-(U5-~{RX1BF}-Pad11)") (class "Default")
      (node (ref "U5") (pin "11") (pinfunction "~{RX1BF}_11") (pintype "bidirectional"))
    )
    (net (code "93") (name "unconnected-(U5-~{TX0RTS}-Pad4)") (class "Default")
      (node (ref "U5") (pin "4") (pinfunction "~{TX0RTS}_4") (pintype "bidirectional"))
    )
    (net (code "94") (name "unconnected-(U5-~{TX1RTS}-Pad5)") (class "Default")
      (node (ref "U5") (pin "5") (pinfunction "~{TX1RTS}_5") (pintype "bidirectional"))
    )
    (net (code "95") (name "unconnected-(U5-~{TX2RTS}-Pad7)") (class "Default")
      (node (ref "U5") (pin "7") (pinfunction "~{TX2RTS}_7") (pintype "bidirectional"))
    )
    (net (code "96") (name "unconnected-(X2-GND-Pad2)") (class "Default")
      (node (ref "X2") (pin "2") (pinfunction "GND_2") (pintype "bidirectional"))
    )
    (net (code "97") (name "unconnected-(X2-GND-Pad4)") (class "Default")
      (node (ref "X2") (pin "4") (pinfunction "GND_4") (pintype "bidirectional"))
    )
  )
)
